# Placa_de_alimenta_o.net
KiCad netlist of a schematic drawn in Altium Designer
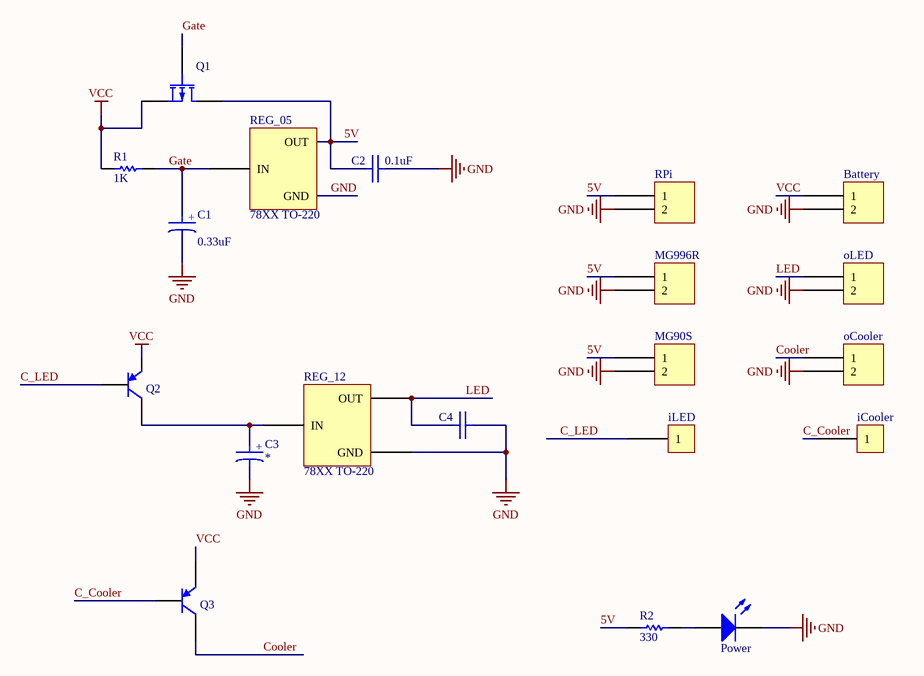
[diagram p0: Placa de alimentação.SchDoc]

(export (version "E")
  (design (tool "Eeschema 10.0.6"))
  (components
    (comp (ref "Battery") (value "*") (footprint "XT90") (libsource (lib "Connectors") (part "XT90")))
    (comp (ref "C1")
      (value "0.33uF")
      (footprint "Eletrolytic Capacitor 5x5mm")
      (libsource (lib "Components") (part "Electrolytic Capacitor 0.33uF"))
    )
    (comp (ref "C2")
      (value "0.1uF")
      (footprint "SMD Capacitor")
      (libsource (lib "Components") (part "Capacitor SMD 0805"))
    )
    (comp (ref "C3")
      (value "*")
      (footprint "Eletrolytic Capacitor 5x5mm")
      (libsource (lib "Components") (part "Electrolytic Capacitor 0.33uF"))
    )
    (comp (ref "C4")
      (value "*")
      (footprint "SMD Capacitor")
      (libsource (lib "Components") (part "Capacitor SMD 0805"))
    )
    (comp (ref "iCooler")
      (value "*")
      (footprint "HEADER 1X1 8.5MM")
      (libsource (lib "Connectors") (part "Male Pin Head 1x1"))
    )
    (comp (ref "iLED")
      (value "*")
      (footprint "HEADER 1X1 8.5MM")
      (libsource (lib "Connectors") (part "Male Pin Head 1x1"))
    )
    (comp (ref "MG90S")
      (value "*")
      (footprint "KK2")
      (description "KK Connector, 2 ways")
      (libsource (lib "Connectors") (part "KK2"))
    )
    (comp (ref "MG996R")
      (value "*")
      (footprint "KK2")
      (description "KK Connector, 2 ways")
      (libsource (lib "Connectors") (part "KK2"))
    )
    (comp (ref "oCooler")
      (value "*")
      (footprint "KK2")
      (description "KK Connector, 2 ways")
      (libsource (lib "Connectors") (part "KK2"))
    )
    (comp (ref "oLED")
      (value "*")
      (footprint "KK2")
      (description "KK Connector, 2 ways")
      (libsource (lib "Connectors") (part "KK2"))
    )
    (comp (ref "Power")
      (value "LED 5mm THT")
      (footprint "LED THT")
      (libsource (lib "Components") (part "LED 5mm THT"))
    )
    (comp (ref "Q1")
      (value "Mosfet P")
      (footprint "TO-252-3")
      (libsource (lib "Components") (part "Mosfet P"))
    )
    (comp (ref "Q2")
      (value "*")
      (footprint "TO-220")
      (libsource (lib "Components") (part "NPN Transistor TO-220"))
    )
    (comp (ref "Q3")
      (value "*")
      (footprint "TO-220")
      (libsource (lib "Components") (part "NPN Transistor TO-220"))
    )
    (comp (ref "R1")
      (value "1K")
      (footprint "RESISTOR THT 5mm")
      (fields (field (name "Comment") "Resistor THT"))
      (libsource (lib "Components") (part "Resistor THT"))
    )
    (comp (ref "R2")
      (value "330")
      (footprint "RESISTOR THT 5mm")
      (fields (field (name "Comment") "Resistor THT"))
      (libsource (lib "Components") (part "Resistor THT"))
    )
    (comp (ref "REG_05")
      (value "78XX TO-220")
      (footprint "TO-220")
      (libsource (lib "Components") (part "78XX TO-220"))
    )
    (comp (ref "REG_12")
      (value "78XX TO-220")
      (footprint "TO-220")
      (libsource (lib "Components") (part "78XX TO-220"))
    )
    (comp (ref "RPi")
      (value "*")
      (footprint "KK2")
      (description "KK Connector, 2 ways")
      (libsource (lib "Connectors") (part "KK2"))
    )
  )
  (nets
    (net (code "1") (name "/5V") (class "Default")
      (node (ref "C2") (pin "2") (pintype "passive"))
      (node (ref "MG90S") (pin "1") (pinfunction "1_1") (pintype "passive"))
      (node (ref "MG996R") (pin "1") (pinfunction "1_1") (pintype "passive"))
      (node (ref "Q1") (pin "2") (pinfunction "D_2") (pintype "passive"))
      (node (ref "R2") (pin "1") (pinfunction "1_1") (pintype "passive"))
      (node (ref "REG_05") (pin "3") (pinfunction "OUT_3") (pintype "passive"))
      (node (ref "RPi") (pin "1") (pinfunction "1_1") (pintype "passive"))
    )
    (net (code "2") (name "/C_Cooler") (class "Default")
      (node (ref "Q3") (pin "3") (pinfunction "B_3") (pintype "passive"))
      (node (ref "iCooler") (pin "1") (pinfunction "1_1") (pintype "passive"))
    )
    (net (code "3") (name "/C_LED") (class "Default")
      (node (ref "Q2") (pin "3") (pinfunction "B_3") (pintype "passive"))
      (node (ref "iLED") (pin "1") (pinfunction "1_1") (pintype "passive"))
    )
    (net (code "4") (name "/Cooler") (class "Default")
      (node (ref "Q3") (pin "2") (pinfunction "C_2") (pintype "passive"))
      (node (ref "oCooler") (pin "1") (pinfunction "1_1") (pintype "passive"))
    )
    (net (code "5") (name "/Gate") (class "Default")
      (node (ref "C1") (pin "1") (pintype "passive"))
      (node (ref "Q1") (pin "1") (pinfunction "G_1") (pintype "passive"))
      (node (ref "R1") (pin "2") (pinfunction "2_2") (pintype "passive"))
      (node (ref "REG_05") (pin "1") (pinfunction "IN_1") (pintype "passive"))
    )
    (net (code "6") (name "/LED") (class "Default")
      (node (ref "C4") (pin "2") (pintype "passive"))
      (node (ref "REG_12") (pin "3") (pinfunction "OUT_3") (pintype "passive"))
      (node (ref "oLED") (pin "1") (pinfunction "1_1") (pintype "passive"))
    )
    (net (code "7") (name "GND") (class "Default")
      (node (ref "Battery") (pin "2") (pinfunction "2_2") (pintype "passive"))
      (node (ref "C1") (pin "2") (pintype "passive"))
      (node (ref "C2") (pin "1") (pintype "passive"))
      (node (ref "C3") (pin "2") (pintype "passive"))
      (node (ref "C4") (pin "1") (pintype "passive"))
      (node (ref "MG90S") (pin "2") (pinfunction "2_2") (pintype "passive"))
      (node (ref "MG996R") (pin "2") (pinfunction "2_2") (pintype "passive"))
      (node (ref "Power") (pin "2") (pinfunction "K_2") (pintype "passive"))
      (node (ref "REG_05") (pin "2") (pinfunction "GND_2") (pintype "passive"))
      (node (ref "REG_12") (pin "2") (pinfunction "GND_2") (pintype "passive"))
      (node (ref "RPi") (pin "2") (pinfunction "2_2") (pintype "passive"))
      (node (ref "oCooler") (pin "2") (pinfunction "2_2") (pintype "passive"))
      (node (ref "oLED") (pin "2") (pinfunction "2_2") (pintype "passive"))
    )
    (net (code "8") (name "Net-(Power-A)") (class "Default")
      (node (ref "Power") (pin "1") (pinfunction "A_1") (pintype "passive"))
      (node (ref "R2") (pin "2") (pinfunction "2_2") (pintype "passive"))
    )
    (net (code "9") (name "Net-(Q2-C)") (class "Default")
      (node (ref "C3") (pin "1") (pintype "passive"))
      (node (ref "Q2") (pin "2") (pinfunction "C_2") (pintype "passive"))
      (node (ref "REG_12") (pin "1") (pinfunction "IN_1") (pintype "passive"))
    )
    (net (code "10") (name "VCC") (class "Default")
      (node (ref "Battery") (pin "1") (pinfunction "1_1") (pintype "passive"))
      (node (ref "Q1") (pin "3") (pinfunction "S_3") (pintype "passive"))
      (node (ref "Q2") (pin "1") (pinfunction "E_1") (pintype "passive"))
      (node (ref "Q3") (pin "1") (pinfunction "E_1") (pintype "passive"))
      (node (ref "R1") (pin "1") (pinfunction "1_1") (pintype "passive"))
    )
  )
)
